# Hex_Link_Trans.net
KiCad netlist of a schematic drawn in Altium Designer
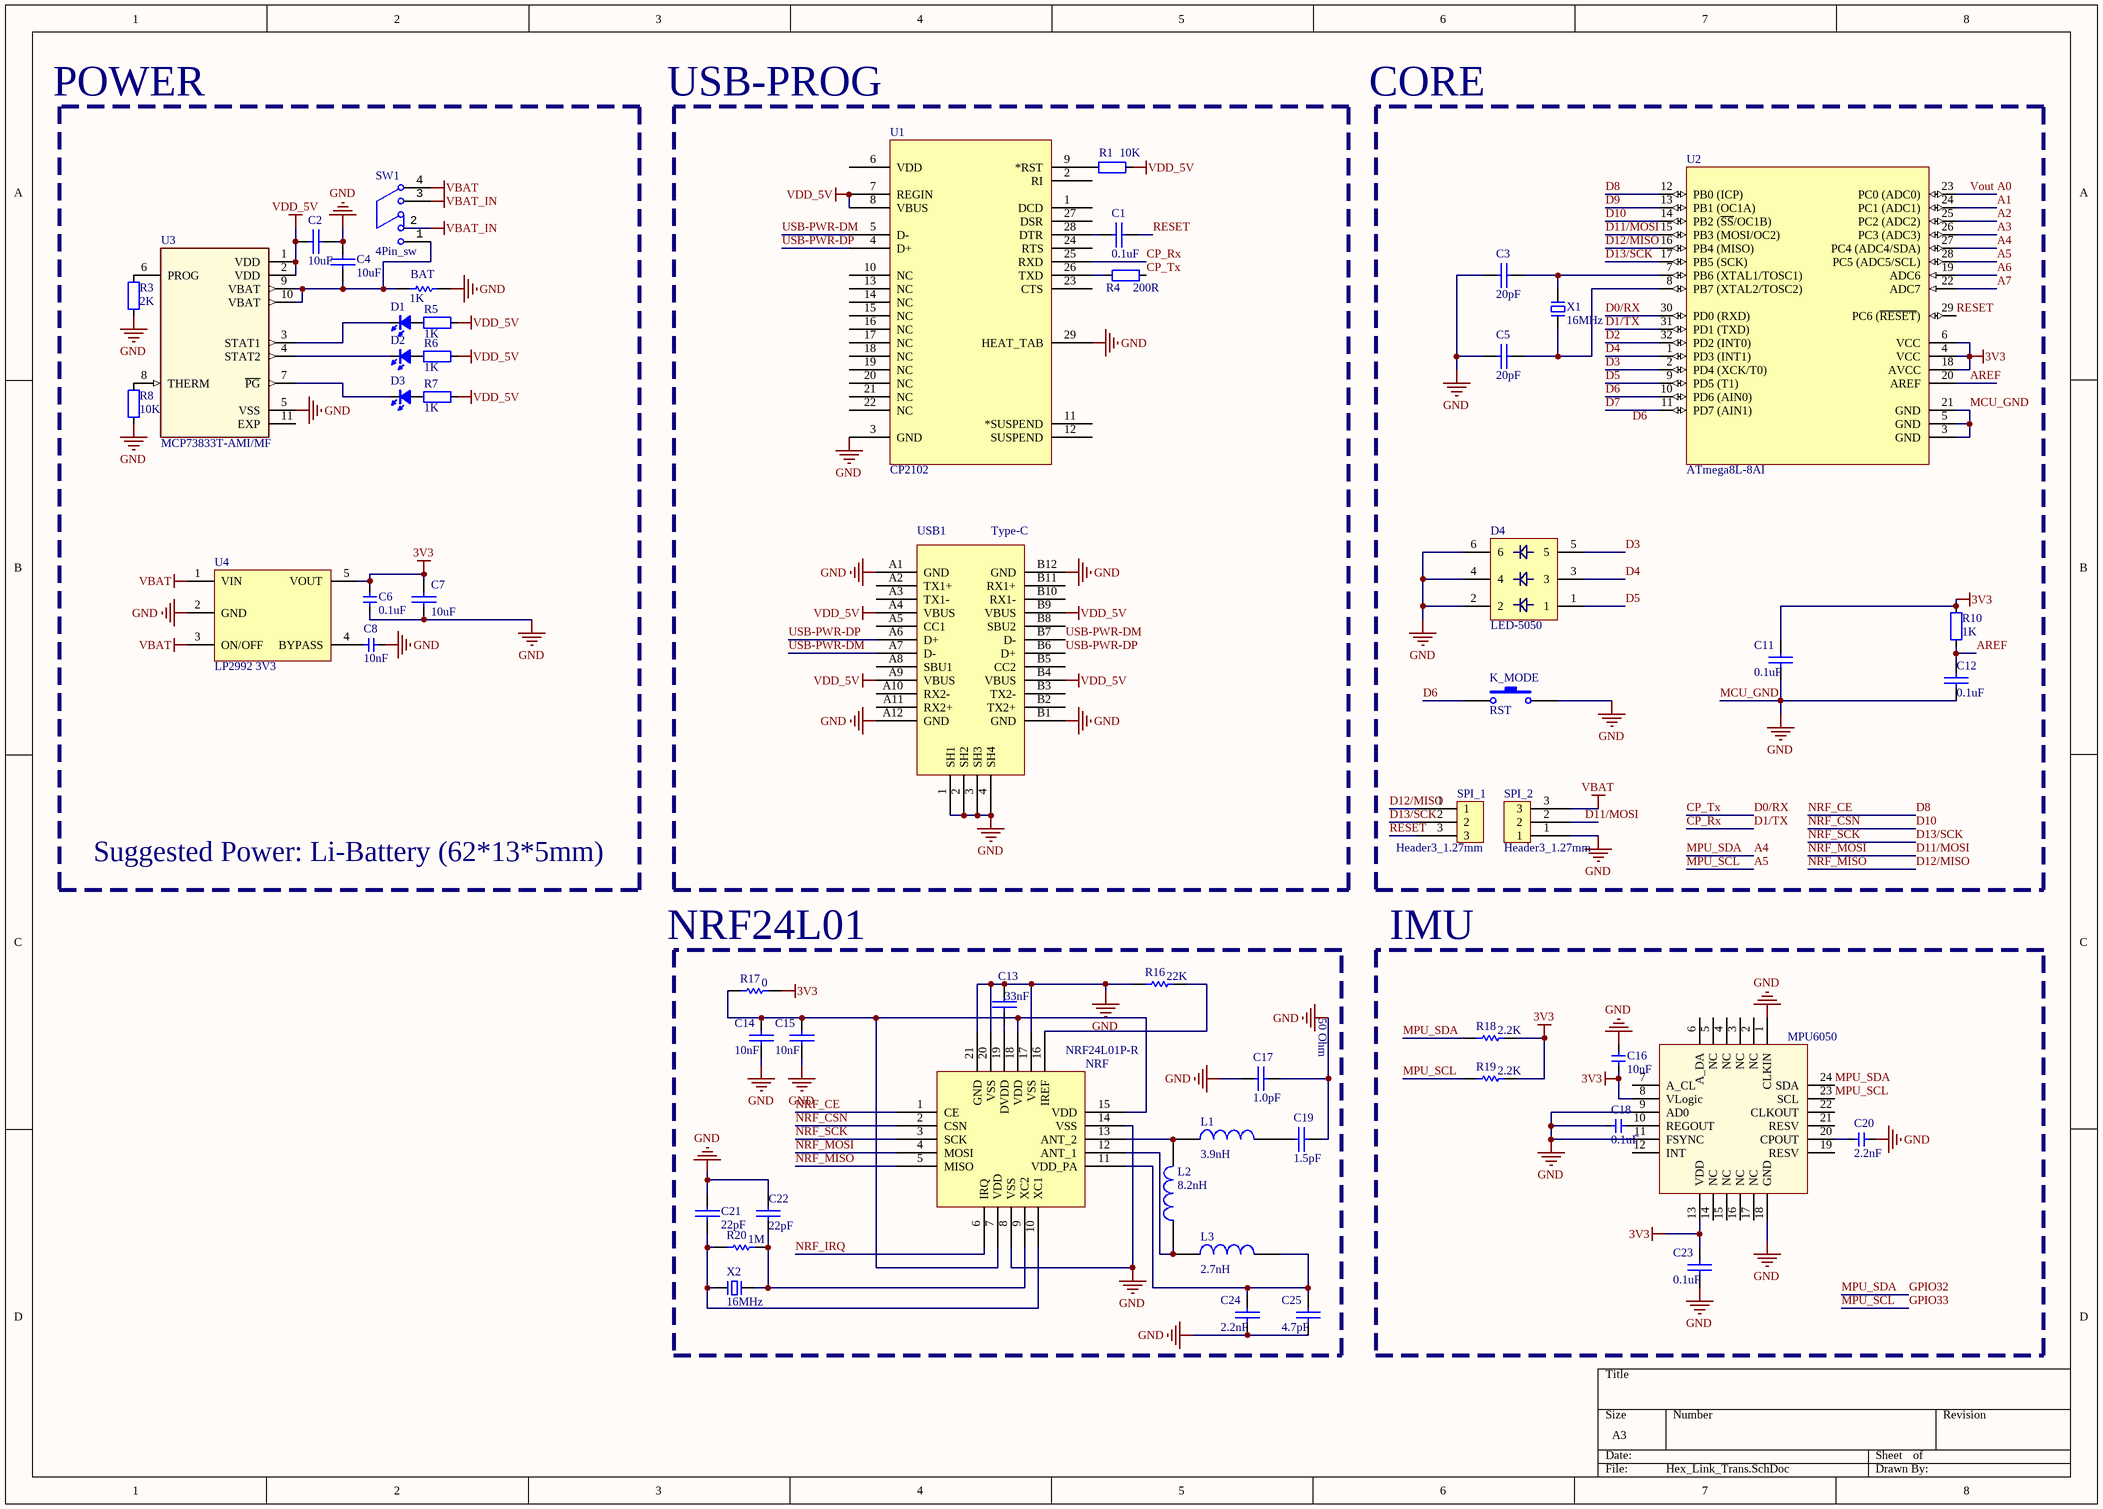
[diagram p0: Hex_Link_Trans.SchDoc]

(export (version "E")
  (design (tool "Eeschema 10.0.6"))
  (components
    (comp (ref "BAT") (value "1K") (footprint "RES_0402") (libsource (lib "电阻") (part "RES")))
    (comp (ref "C1")
      (value "0.1uF")
      (footprint "CAP_0402")
      (description "无极性电容")
      (libsource (lib "电容") (part "CAP"))
    )
    (comp (ref "C2")
      (value "10uF")
      (footprint "CAP_0402")
      (description "无极性电容")
      (libsource (lib "电容") (part "CAP"))
    )
    (comp (ref "C3")
      (value "20pF")
      (footprint "CAP_0402")
      (description "无极性电容")
      (libsource (lib "电容") (part "CAP"))
    )
    (comp (ref "C4")
      (value "10uF")
      (footprint "CAP_0402")
      (description "无极性电容")
      (libsource (lib "电容") (part "CAP"))
    )
    (comp (ref "C5")
      (value "20pF")
      (footprint "CAP_0402")
      (description "无极性电容")
      (libsource (lib "电容") (part "CAP"))
    )
    (comp (ref "C6")
      (value "0.1uF")
      (footprint "CAP_0402")
      (description "Capacitor")
      (libsource (lib "MyPcbLib") (part "电容-0402"))
    )
    (comp (ref "C7")
      (value "10uF")
      (footprint "CAP_0402")
      (description "无极性电容")
      (libsource (lib "电容") (part "CAP"))
    )
    (comp (ref "C8")
      (value "10nF")
      (footprint "CAP_0402")
      (description "Capacitor")
      (libsource (lib "MyPcbLib") (part "电容-0402"))
    )
    (comp (ref "C11")
      (value "0.1uF")
      (footprint "CAP_0402")
      (description "无极性电容")
      (libsource (lib "电容") (part "CAP"))
    )
    (comp (ref "C12")
      (value "0.1uF")
      (footprint "CAP_0402")
      (description "无极性电容")
      (libsource (lib "电容") (part "CAP"))
    )
    (comp (ref "C13")
      (value "33nF")
      (footprint "CAP_0402")
      (description "无极性电容")
      (libsource (lib "电容") (part "CAP"))
    )
    (comp (ref "C14")
      (value "10nF")
      (footprint "CAP_0402")
      (description "无极性电容")
      (libsource (lib "电容") (part "CAP"))
    )
    (comp (ref "C15")
      (value "10nF")
      (footprint "CAP_0402")
      (description "无极性电容")
      (libsource (lib "电容") (part "CAP"))
    )
    (comp (ref "C16")
      (value "10nF")
      (footprint "CAP_0402")
      (description "Capacitor")
      (libsource (lib "MyPcbLib") (part "电容-0402"))
    )
    (comp (ref "C17")
      (value "1.0pF")
      (footprint "CAP_0402")
      (description "无极性电容")
      (libsource (lib "电容") (part "CAP"))
    )
    (comp (ref "C18")
      (value "0.1uF")
      (footprint "CAP_0402")
      (description "Capacitor")
      (libsource (lib "MyPcbLib") (part "电容-0402"))
    )
    (comp (ref "C19")
      (value "1.5pF")
      (footprint "CAP_0402")
      (description "无极性电容")
      (libsource (lib "电容") (part "CAP"))
    )
    (comp (ref "C20")
      (value "2.2nF")
      (footprint "CAP_0402")
      (description "Capacitor")
      (libsource (lib "MyPcbLib") (part "电容-0402"))
    )
    (comp (ref "C21")
      (value "22pF")
      (footprint "CAP_0402")
      (description "无极性电容")
      (libsource (lib "电容") (part "CAP"))
    )
    (comp (ref "C22")
      (value "22pF")
      (footprint "CAP_0402")
      (description "无极性电容")
      (libsource (lib "电容") (part "CAP"))
    )
    (comp (ref "C23")
      (value "0.1uF")
      (footprint "CAP_0402")
      (description "无极性电容")
      (libsource (lib "电容") (part "CAP"))
    )
    (comp (ref "C24")
      (value "2.2nF")
      (footprint "CAP_0402")
      (description "无极性电容")
      (libsource (lib "电容") (part "CAP"))
    )
    (comp (ref "C25")
      (value "4.7pF")
      (footprint "CAP_0402")
      (description "无极性电容")
      (libsource (lib "电容") (part "CAP"))
    )
    (comp (ref "D1")
      (value "color?")
      (footprint "LED_0402_RED")
      (description "LED")
      (libsource (lib "KitSprout") (part "LED_0402"))
    )
    (comp (ref "D2")
      (value "color?")
      (footprint "LED_0402_RED")
      (description "LED")
      (libsource (lib "KitSprout") (part "LED_0402"))
    )
    (comp (ref "D3")
      (value "color?")
      (footprint "LED_0402_RED")
      (description "LED")
      (libsource (lib "KitSprout") (part "LED_0402"))
    )
    (comp (ref "D4") (value "LED-5050") (footprint "LED-5050W") (libsource (lib "LED") (part "LED-5050")))
    (comp (ref "K_MODE")
      (value "RST")
      (footprint "SW_PB")
      (description "Switch")
      (fields (field (name "PUBLISHER") "Altium Limited"))
      (libsource (lib "未分类IC") (part "SW-PB"))
    )
    (comp (ref "L1")
      (value "3.9nH")
      (footprint "0402L_2")
      (description "INDUCTOR")
      (libsource (lib "") (part "INDUCTOR_1"))
    )
    (comp (ref "L2")
      (value "8.2nH")
      (footprint "0402L_2")
      (description "INDUCTOR")
      (libsource (lib "电感") (part "INDUCTOR"))
    )
    (comp (ref "L3")
      (value "2.7nH")
      (footprint "0402L_2")
      (description "INDUCTOR")
      (libsource (lib "") (part "INDUCTOR_1"))
    )
    (comp (ref "NRF")
      (value "NRF24L01P-R")
      (footprint "QFN20")
      (libsource (lib "未分类IC") (part "NRF24L01P-R"))
    )
    (comp (ref "R1")
      (value "10K")
      (footprint "RES_0402")
      (description "Resistor")
      (libsource (lib "MyPcbLib") (part "电阻-0402"))
    )
    (comp (ref "R3")
      (value "2K")
      (footprint "RES_0402")
      (description "Resistor")
      (libsource (lib "") (part "电阻-0402_1"))
    )
    (comp (ref "R4")
      (value "200R")
      (footprint "RES_0402")
      (description "Resistor")
      (libsource (lib "MyPcbLib") (part "电阻-0402"))
    )
    (comp (ref "R5")
      (value "1K")
      (footprint "RES_0402")
      (description "Resistor")
      (libsource (lib "MyPcbLib") (part "电阻-0402"))
    )
    (comp (ref "R6")
      (value "1K")
      (footprint "RES_0402")
      (description "Resistor")
      (libsource (lib "MyPcbLib") (part "电阻-0402"))
    )
    (comp (ref "R7")
      (value "1K")
      (footprint "RES_0402")
      (description "Resistor")
      (libsource (lib "MyPcbLib") (part "电阻-0402"))
    )
    (comp (ref "R8")
      (value "10K")
      (footprint "RES_0402")
      (description "Resistor")
      (libsource (lib "") (part "电阻-0402_1"))
    )
    (comp (ref "R10")
      (value "1K")
      (footprint "RES_0402")
      (description "Resistor")
      (libsource (lib "") (part "电阻-0402_2"))
    )
    (comp (ref "R16") (value "22K") (footprint "RES_0402") (libsource (lib "电阻") (part "RES")))
    (comp (ref "R17") (value "0") (footprint "RES_0402") (libsource (lib "电阻") (part "RES")))
    (comp (ref "R18") (value "2.2K") (footprint "RES_0402") (libsource (lib "电阻") (part "RES")))
    (comp (ref "R19") (value "2.2K") (footprint "RES_0402") (libsource (lib "电阻") (part "RES")))
    (comp (ref "R20") (value "1M") (footprint "RES_0402") (libsource (lib "电阻") (part "RES")))
    (comp (ref "SPI_1")
      (value "Header3_1.27mm")
      (footprint "HEADER3_1.27mm")
      (libsource (lib "") (part "Header3_1.27mm_1"))
    )
    (comp (ref "SPI_2")
      (value "Header3_1.27mm")
      (footprint "HEADER3_1.27mm")
      (libsource (lib "未分类IC") (part "Header3_1.27mm"))
    )
    (comp (ref "SW1") (value "4Pin_sw") (footprint "4pin_SW") (libsource (lib "未分类IC") (part "4Pin_sw")))
    (comp (ref "U1")
      (value "CP2102")
      (footprint "QFN-28")
      (description "USB转TTL")
      (libsource (lib "mLib") (part "CP2102"))
    )
    (comp (ref "U2")
      (value "ATmega8L-8AI")
      (footprint "32A_N")
      (description "8-Bit AVR Microcontroller with 8K Bytes of In-System Programmable Flash Memory")
      (fields (field (name "PUBLISHER") "Altium Limited"))
      (libsource (lib "Atmel Microcontroller 8-Bit AVR") (part "ATmega8L-8AI"))
    )
    (comp (ref "U3")
      (value "MCP73833T-AMI/MF")
      (footprint "QFN_10_L")
      (description "Linear Charge Management Controller Li-Ion/Li-Pol 1mA 4.2V/4.35V/4.4V/4.5V 10-Pin DFN EP T/R")
      (fields (field (name "MF") "Microchip"))
      (libsource (lib "mLib") (part "MCP73833T"))
    )
    (comp (ref "U4")
      (value "LP2992 3V3")
      (footprint "SOT23-5")
      (description "LDO")
      (libsource (lib "MyPcbLib") (part "LP2992"))
    )
    (comp (ref "U5")
      (value "MPU6050")
      (footprint "QFN-24")
      (description "六轴传感器")
      (libsource (lib "mLib") (part "MPU6050"))
    )
    (comp (ref "USB1")
      (value "Type-C")
      (footprint "Type-C-TOP")
      (libsource (lib "MyPcbLib") (part "USB-Type-C-TOP"))
    )
    (comp (ref "X1")
      (value "16MHz")
      (footprint "OSC 5032-2P")
      (description "2脚无源脚晶振")
      (libsource (lib "晶振") (part "XTAL-2P"))
    )
    (comp (ref "X2")
      (value "16MHz")
      (footprint "OSC 5032-2P")
      (description "2脚无源脚晶振")
      (libsource (lib "晶振") (part "XTAL-2P"))
    )
  )
  (nets
    (net (code "1") (name "/A0") (class "Default")
      (node (ref "U2") (pin "23") (pinfunction "PC0_(ADC0)_23") (pintype "bidirectional"))
    )
    (net (code "2") (name "/A1") (class "Default")
      (node (ref "U2") (pin "24") (pinfunction "PC1_(ADC1)_24") (pintype "bidirectional"))
    )
    (net (code "3") (name "/A2") (class "Default")
      (node (ref "U2") (pin "25") (pinfunction "PC2_(ADC2)_25") (pintype "bidirectional"))
    )
    (net (code "4") (name "/A3") (class "Default")
      (node (ref "U2") (pin "26") (pinfunction "PC3_(ADC3)_26") (pintype "bidirectional"))
    )
    (net (code "5") (name "/A4") (class "Default")
      (node (ref "R18") (pin "1") (pinfunction "1_1") (pintype "passive"))
      (node (ref "U2") (pin "27") (pinfunction "PC4_(ADC4/SDA)_27") (pintype "bidirectional"))
      (node (ref "U5") (pin "24") (pinfunction "SDA_24") (pintype "passive"))
    )
    (net (code "6") (name "/A5") (class "Default")
      (node (ref "R19") (pin "1") (pinfunction "1_1") (pintype "passive"))
      (node (ref "U2") (pin "28") (pinfunction "PC5_(ADC5/SCL)_28") (pintype "bidirectional"))
      (node (ref "U5") (pin "23") (pinfunction "SCL_23") (pintype "passive"))
    )
    (net (code "7") (name "/A6") (class "Default")
      (node (ref "U2") (pin "19") (pinfunction "ADC6_19") (pintype "input"))
    )
    (net (code "8") (name "/A7") (class "Default")
      (node (ref "U2") (pin "22") (pinfunction "ADC7_22") (pintype "input"))
    )
    (net (code "9") (name "/AREF") (class "Default")
      (node (ref "C12") (pin "1") (pinfunction "1_1") (pintype "passive"))
      (node (ref "R10") (pin "2") (pinfunction "2_2") (pintype "passive"))
      (node (ref "U2") (pin "20") (pinfunction "AREF_20") (pintype "passive"))
    )
    (net (code "10") (name "/CP_Rx") (class "Default")
      (node (ref "U1") (pin "25") (pinfunction "RXD_25") (pintype "passive"))
      (node (ref "U2") (pin "31") (pinfunction "PD1_(TXD)_31") (pintype "bidirectional"))
    )
    (net (code "11") (name "/CP_Tx") (class "Default")
      (node (ref "R4") (pin "1") (pinfunction "1_1") (pintype "passive"))
      (node (ref "U2") (pin "30") (pinfunction "PD0_(RXD)_30") (pintype "bidirectional"))
    )
    (net (code "12") (name "/D2") (class "Default")
      (node (ref "U2") (pin "32") (pinfunction "PD2_(INT0)_32") (pintype "bidirectional"))
    )
    (net (code "13") (name "/D3") (class "Default")
      (node (ref "D4") (pin "5") (pinfunction "5_5") (pintype "passive"))
      (node (ref "U2") (pin "2") (pinfunction "PD4_(XCK/T0)_2") (pintype "bidirectional"))
    )
    (net (code "14") (name "/D4") (class "Default")
      (node (ref "D4") (pin "3") (pinfunction "3_3") (pintype "passive"))
      (node (ref "U2") (pin "1") (pinfunction "PD3_(INT1)_1") (pintype "bidirectional"))
    )
    (net (code "15") (name "/D5") (class "Default")
      (node (ref "D4") (pin "1") (pinfunction "1_1") (pintype "passive"))
      (node (ref "U2") (pin "9") (pinfunction "PD5_(T1)_9") (pintype "bidirectional"))
    )
    (net (code "16") (name "/D6") (class "Default")
      (node (ref "K_MODE") (pin "1") (pinfunction "1_1") (pintype "passive"))
      (node (ref "U2") (pin "10") (pinfunction "PD6_(AIN0)_10") (pintype "bidirectional"))
    )
    (net (code "17") (name "/D7") (class "Default")
      (node (ref "U2") (pin "11") (pinfunction "PD7_(AIN1)_11") (pintype "bidirectional"))
    )
    (net (code "18") (name "/D8") (class "Default")
      (node (ref "NRF") (pin "1") (pinfunction "CE_1") (pintype "passive"))
      (node (ref "U2") (pin "12") (pinfunction "PB0_(ICP)_12") (pintype "bidirectional"))
    )
    (net (code "19") (name "/D9") (class "Default")
      (node (ref "U2") (pin "13") (pinfunction "PB1_(OC1A)_13") (pintype "bidirectional"))
    )
    (net (code "20") (name "/D10") (class "Default")
      (node (ref "NRF") (pin "2") (pinfunction "CSN_2") (pintype "passive"))
      (node (ref "U2") (pin "14") (pinfunction "PB2_(~{SS}/OC1B)_14") (pintype "bidirectional"))
    )
    (net (code "21") (name "/D11{slash}MOSI") (class "Default")
      (node (ref "NRF") (pin "4") (pinfunction "MOSI_4") (pintype "passive"))
      (node (ref "SPI_2") (pin "2") (pinfunction "2_2") (pintype "passive"))
      (node (ref "U2") (pin "15") (pinfunction "PB3_(MOSI/OC2)_15") (pintype "bidirectional"))
    )
    (net (code "22") (name "/D12{slash}MISO") (class "Default")
      (node (ref "NRF") (pin "5") (pinfunction "MISO_5") (pintype "passive"))
      (node (ref "SPI_1") (pin "1") (pinfunction "1_1") (pintype "passive"))
      (node (ref "U2") (pin "16") (pinfunction "PB4_(MISO)_16") (pintype "bidirectional"))
    )
    (net (code "23") (name "/D13{slash}SCK") (class "Default")
      (node (ref "NRF") (pin "3") (pinfunction "SCK_3") (pintype "passive"))
      (node (ref "SPI_1") (pin "2") (pinfunction "2_2") (pintype "passive"))
      (node (ref "U2") (pin "17") (pinfunction "PB5_(SCK)_17") (pintype "bidirectional"))
    )
    (net (code "24") (name "/NRF_IRQ") (class "Default")
      (node (ref "NRF") (pin "6") (pinfunction "IRQ_6") (pintype "passive"))
    )
    (net (code "25") (name "/RESET") (class "Default")
      (node (ref "C1") (pin "1") (pinfunction "1_1") (pintype "passive"))
      (node (ref "SPI_1") (pin "3") (pinfunction "3_3") (pintype "passive"))
      (node (ref "U2") (pin "29") (pinfunction "PC6_(~{RESET})_29") (pintype "bidirectional"))
    )
    (net (code "26") (name "/USB-PWR-DM") (class "Default")
      (node (ref "U1") (pin "5") (pinfunction "D-_5") (pintype "passive"))
      (node (ref "USB1") (pin "A7") (pinfunction "D-_A7") (pintype "passive"))
      (node (ref "USB1") (pin "B7") (pinfunction "D-_B7") (pintype "passive"))
    )
    (net (code "27") (name "/USB-PWR-DP") (class "Default")
      (node (ref "U1") (pin "4") (pinfunction "D+_4") (pintype "passive"))
      (node (ref "USB1") (pin "A6") (pinfunction "D+_A6") (pintype "passive"))
      (node (ref "USB1") (pin "B6") (pinfunction "D+_B6") (pintype "passive"))
    )
    (net (code "28") (name "3V3") (class "Default")
      (node (ref "C11") (pin "1") (pinfunction "1_1") (pintype "passive"))
      (node (ref "C16") (pin "1") (pinfunction "1_1") (pintype "passive"))
      (node (ref "C23") (pin "1") (pinfunction "1_1") (pintype "passive"))
      (node (ref "C6") (pin "1") (pinfunction "1_1") (pintype "passive"))
      (node (ref "C7") (pin "1") (pinfunction "1_1") (pintype "passive"))
      (node (ref "R10") (pin "1") (pinfunction "1_1") (pintype "passive"))
      (node (ref "R17") (pin "2") (pinfunction "2_2") (pintype "passive"))
      (node (ref "R18") (pin "2") (pinfunction "2_2") (pintype "passive"))
      (node (ref "R19") (pin "2") (pinfunction "2_2") (pintype "passive"))
      (node (ref "U2") (pin "18") (pinfunction "AVCC_18") (pintype "power_in"))
      (node (ref "U2") (pin "4") (pinfunction "VCC_4") (pintype "power_in"))
      (node (ref "U2") (pin "6") (pinfunction "VCC_6") (pintype "power_in"))
      (node (ref "U4") (pin "5") (pinfunction "VOUT_5") (pintype "passive"))
      (node (ref "U5") (pin "13") (pinfunction "VDD_13") (pintype "passive"))
      (node (ref "U5") (pin "8") (pinfunction "VLogic_8") (pintype "passive"))
    )
    (net (code "29") (name "GND") (class "Default")
      (node (ref "BAT") (pin "2") (pinfunction "2_2") (pintype "passive"))
      (node (ref "C11") (pin "2") (pinfunction "2_2") (pintype "passive"))
      (node (ref "C12") (pin "2") (pinfunction "2_2") (pintype "passive"))
      (node (ref "C13") (pin "1") (pinfunction "1_1") (pintype "passive"))
      (node (ref "C14") (pin "2") (pinfunction "2_2") (pintype "passive"))
      (node (ref "C15") (pin "2") (pinfunction "2_2") (pintype "passive"))
      (node (ref "C16") (pin "2") (pinfunction "2_2") (pintype "passive"))
      (node (ref "C17") (pin "1") (pinfunction "1_1") (pintype "passive"))
      (node (ref "C17") (pin "2") (pinfunction "2_2") (pintype "passive"))
      (node (ref "C18") (pin "2") (pinfunction "2_2") (pintype "passive"))
      (node (ref "C19") (pin "2") (pinfunction "2_2") (pintype "passive"))
      (node (ref "C2") (pin "2") (pinfunction "2_2") (pintype "passive"))
      (node (ref "C20") (pin "1") (pinfunction "1_1") (pintype "passive"))
      (node (ref "C21") (pin "2") (pinfunction "2_2") (pintype "passive"))
      (node (ref "C22") (pin "1") (pinfunction "1_1") (pintype "passive"))
      (node (ref "C23") (pin "2") (pinfunction "2_2") (pintype "passive"))
      (node (ref "C24") (pin "2") (pinfunction "2_2") (pintype "passive"))
      (node (ref "C25") (pin "2") (pinfunction "2_2") (pintype "passive"))
      (node (ref "C3") (pin "2") (pinfunction "2_2") (pintype "passive"))
      (node (ref "C4") (pin "1") (pinfunction "1_1") (pintype "passive"))
      (node (ref "C5") (pin "2") (pinfunction "2_2") (pintype "passive"))
      (node (ref "C6") (pin "2") (pinfunction "2_2") (pintype "passive"))
      (node (ref "C7") (pin "2") (pinfunction "2_2") (pintype "passive"))
      (node (ref "C8") (pin "1") (pinfunction "1_1") (pintype "passive"))
      (node (ref "D4") (pin "2") (pinfunction "2_2") (pintype "passive"))
      (node (ref "D4") (pin "4") (pinfunction "4_4") (pintype "passive"))
      (node (ref "D4") (pin "6") (pinfunction "6_6") (pintype "passive"))
      (node (ref "K_MODE") (pin "2") (pinfunction "2_2") (pintype "passive"))
      (node (ref "NRF") (pin "14") (pinfunction "VSS_14") (pintype "passive"))
      (node (ref "NRF") (pin "17") (pinfunction "VSS_17") (pintype "passive"))
      (node (ref "NRF") (pin "20") (pinfunction "VSS_20") (pintype "passive"))
      (node (ref "NRF") (pin "21") (pinfunction "GND_21") (pintype "passive"))
      (node (ref "NRF") (pin "8") (pinfunction "VSS_8") (pintype "passive"))
      (node (ref "R16") (pin "1") (pinfunction "1_1") (pintype "passive"))
      (node (ref "R3") (pin "1") (pinfunction "1_1") (pintype "passive"))
      (node (ref "R8") (pin "1") (pinfunction "1_1") (pintype "passive"))
      (node (ref "SPI_2") (pin "1") (pinfunction "1_1") (pintype "passive"))
      (node (ref "U1") (pin "29") (pinfunction "HEAT_TAB_29") (pintype "passive"))
      (node (ref "U1") (pin "3") (pinfunction "GND_3") (pintype "passive"))
      (node (ref "U2") (pin "21") (pinfunction "GND_21") (pintype "power_in"))
      (node (ref "U2") (pin "3") (pinfunction "GND_3") (pintype "power_in"))
      (node (ref "U2") (pin "5") (pinfunction "GND_5") (pintype "power_in"))
      (node (ref "U3") (pin "5") (pinfunction "VSS_5") (pintype "power_in"))
      (node (ref "U4") (pin "2") (pinfunction "GND_2") (pintype "passive"))
      (node (ref "U5") (pin "1") (pinfunction "CLKIN_1") (pintype "passive"))
      (node (ref "U5") (pin "11") (pinfunction "FSYNC_11") (pintype "passive"))
      (node (ref "U5") (pin "18") (pinfunction "GND_18") (pintype "passive"))
      (node (ref "U5") (pin "9") (pinfunction "AD0_9") (pintype "passive"))
      (node (ref "USB1") (pin "1") (pinfunction "SH1_1") (pintype "passive"))
      (node (ref "USB1") (pin "2") (pinfunction "SH2_2") (pintype "passive"))
      (node (ref "USB1") (pin "3") (pinfunction "SH3_3") (pintype "passive"))
      (node (ref "USB1") (pin "4") (pinfunction "SH4_4") (pintype "passive"))
      (node (ref "USB1") (pin "A1") (pinfunction "GND_A1") (pintype "passive"))
      (node (ref "USB1") (pin "A12") (pinfunction "GND_A12") (pintype "passive"))
      (node (ref "USB1") (pin "B1") (pinfunction "GND_B1") (pintype "passive"))
      (node (ref "USB1") (pin "B12") (pinfunction "GND_B12") (pintype "passive"))
    )
    (net (code "30") (name "Net-(BAT-Pad1)") (class "Default")
      (node (ref "BAT") (pin "1") (pinfunction "1_1") (pintype "passive"))
      (node (ref "C4") (pin "2") (pinfunction "2_2") (pintype "passive"))
      (node (ref "SW1") (pin "1") (pinfunction "1_1") (pintype "passive"))
      (node (ref "U3") (pin "10") (pinfunction "VBAT_10") (pintype "output"))
      (node (ref "U3") (pin "9") (pinfunction "VBAT_9") (pintype "output"))
    )
    (net (code "31") (name "Net-(C14-Pad1)") (class "Default")
      (node (ref "C14") (pin "1") (pinfunction "1_1") (pintype "passive"))
      (node (ref "C15") (pin "1") (pinfunction "1_1") (pintype "passive"))
      (node (ref "NRF") (pin "15") (pinfunction "VDD_15") (pintype "passive"))
      (node (ref "NRF") (pin "18") (pinfunction "VDD_18") (pintype "passive"))
      (node (ref "NRF") (pin "7") (pinfunction "VDD_7") (pintype "passive"))
      (node (ref "R17") (pin "1") (pinfunction "1_1") (pintype "passive"))
    )
    (net (code "32") (name "Net-(C19-Pad1)") (class "Default")
      (node (ref "C19") (pin "1") (pinfunction "1_1") (pintype "passive"))
      (node (ref "L1") (pin "2") (pinfunction "2_2") (pintype "passive"))
    )
    (net (code "33") (name "Net-(D1-A)") (class "Default")
      (node (ref "D1") (pin "1") (pinfunction "A_1") (pintype "passive"))
      (node (ref "R5") (pin "2") (pinfunction "2_2") (pintype "passive"))
    )
    (net (code "34") (name "Net-(D1-K)") (class "Default")
      (node (ref "D1") (pin "2") (pinfunction "K_2") (pintype "passive"))
      (node (ref "U3") (pin "3") (pinfunction "STAT1_3") (pintype "output"))
    )
    (net (code "35") (name "Net-(D2-A)") (class "Default")
      (node (ref "D2") (pin "1") (pinfunction "A_1") (pintype "passive"))
      (node (ref "R6") (pin "2") (pinfunction "2_2") (pintype "passive"))
    )
    (net (code "36") (name "Net-(D2-K)") (class "Default")
      (node (ref "D2") (pin "2") (pinfunction "K_2") (pintype "passive"))
      (node (ref "U3") (pin "4") (pinfunction "STAT2_4") (pintype "output"))
    )
    (net (code "37") (name "Net-(D3-A)") (class "Default")
      (node (ref "D3") (pin "1") (pinfunction "A_1") (pintype "passive"))
      (node (ref "R7") (pin "2") (pinfunction "2_2") (pintype "passive"))
    )
    (net (code "38") (name "Net-(D3-K)") (class "Default")
      (node (ref "D3") (pin "2") (pinfunction "K_2") (pintype "passive"))
      (node (ref "U3") (pin "7") (pinfunction "~{PG}_7") (pintype "output"))
    )
    (net (code "39") (name "Net-(NRF-ANT_1)") (class "Default")
      (node (ref "L2") (pin "1") (pinfunction "1_1") (pintype "passive"))
      (node (ref "L3") (pin "1") (pinfunction "1_1") (pintype "passive"))
      (node (ref "NRF") (pin "12") (pinfunction "ANT_1_12") (pintype "passive"))
    )
    (net (code "40") (name "Net-(NRF-ANT_2)") (class "Default")
      (node (ref "L1") (pin "1") (pinfunction "1_1") (pintype "passive"))
      (node (ref "L2") (pin "2") (pinfunction "2_2") (pintype "passive"))
      (node (ref "NRF") (pin "13") (pinfunction "ANT_2_13") (pintype "passive"))
    )
    (net (code "41") (name "Net-(NRF-DVDD)") (class "Default")
      (node (ref "C13") (pin "2") (pinfunction "2_2") (pintype "passive"))
      (node (ref "NRF") (pin "19") (pinfunction "DVDD_19") (pintype "passive"))
    )
    (net (code "42") (name "Net-(NRF-IREF)") (class "Default")
      (node (ref "NRF") (pin "16") (pinfunction "IREF_16") (pintype "passive"))
      (node (ref "R16") (pin "2") (pinfunction "2_2") (pintype "passive"))
    )
    (net (code "43") (name "Net-(NRF-VDD_PA)") (class "Default")
      (node (ref "C24") (pin "1") (pinfunction "1_1") (pintype "passive"))
      (node (ref "C25") (pin "1") (pinfunction "1_1") (pintype "passive"))
      (node (ref "L3") (pin "2") (pinfunction "2_2") (pintype "passive"))
      (node (ref "NRF") (pin "11") (pinfunction "VDD_PA_11") (pintype "passive"))
    )
    (net (code "44") (name "Net-(NRF-XC1)") (class "Default")
      (node (ref "C21") (pin "1") (pinfunction "1_1") (pintype "passive"))
      (node (ref "NRF") (pin "10") (pinfunction "XC1_10") (pintype "passive"))
      (node (ref "R20") (pin "1") (pinfunction "1_1") (pintype "passive"))
      (node (ref "X2") (pin "1") (pinfunction "1_1") (pintype "passive"))
    )
    (net (code "45") (name "Net-(NRF-XC2)") (class "Default")
      (node (ref "C22") (pin "2") (pinfunction "2_2") (pintype "passive"))
      (node (ref "NRF") (pin "9") (pinfunction "XC2_9") (pintype "passive"))
      (node (ref "R20") (pin "2") (pinfunction "2_2") (pintype "passive"))
      (node (ref "X2") (pin "2") (pinfunction "2_2") (pintype "passive"))
    )
    (net (code "46") (name "Net-(U1-*RST)") (class "Default")
      (node (ref "R1") (pin "2") (pinfunction "2_2") (pintype "passive"))
      (node (ref "U1") (pin "9") (pinfunction "*RST_9") (pintype "passive"))
    )
    (net (code "47") (name "Net-(U1-DTR)") (class "Default")
      (node (ref "C1") (pin "2") (pinfunction "2_2") (pintype "passive"))
      (node (ref "U1") (pin "28") (pinfunction "DTR_28") (pintype "passive"))
    )
    (net (code "48") (name "Net-(U1-TXD)") (class "Default")
      (node (ref "R4") (pin "2") (pinfunction "2_2") (pintype "passive"))
      (node (ref "U1") (pin "26") (pinfunction "TXD_26") (pintype "passive"))
    )
    (net (code "49") (name "Net-(U2-PB6_(XTAL1{slash}TOSC1))") (class "Default")
      (node (ref "C3") (pin "1") (pinfunction "1_1") (pintype "passive"))
      (node (ref "U2") (pin "7") (pinfunction "PB6_(XTAL1/TOSC1)_7") (pintype "bidirectional"))
      (node (ref "X1") (pin "2") (pinfunction "2_2") (pintype "passive"))
    )
    (net (code "50") (name "Net-(U2-PB7_(XTAL2{slash}TOSC2))") (class "Default")
      (node (ref "C5") (pin "1") (pinfunction "1_1") (pintype "passive"))
      (node (ref "U2") (pin "8") (pinfunction "PB7_(XTAL2/TOSC2)_8") (pintype "bidirectional"))
      (node (ref "X1") (pin "1") (pinfunction "1_1") (pintype "passive"))
    )
    (net (code "51") (name "Net-(U3-PROG)") (class "Default")
      (node (ref "R3") (pin "2") (pinfunction "2_2") (pintype "passive"))
      (node (ref "U3") (pin "6") (pinfunction "PROG_6") (pintype "passive"))
    )
    (net (code "52") (name "Net-(U3-THERM)") (class "Default")
      (node (ref "R8") (pin "2") (pinfunction "2_2") (pintype "passive"))
      (node (ref "U3") (pin "8") (pinfunction "THERM_8") (pintype "input"))
    )
    (net (code "53") (name "Net-(U4-BYPASS)") (class "Default")
      (node (ref "C8") (pin "2") (pinfunction "2_2") (pintype "passive"))
      (node (ref "U4") (pin "4") (pinfunction "BYPASS_4") (pintype "passive"))
    )
    (net (code "54") (name "Net-(U5-CPOUT)") (class "Default")
      (node (ref "C20") (pin "2") (pinfunction "2_2") (pintype "passive"))
      (node (ref "U5") (pin "20") (pinfunction "CPOUT_20") (pintype "passive"))
    )
    (net (code "55") (name "Net-(U5-REGOUT)") (class "Default")
      (node (ref "C18") (pin "1") (pinfunction "1_1") (pintype "passive"))
      (node (ref "U5") (pin "10") (pinfunction "REGOUT_10") (pintype "passive"))
    )
    (net (code "56") (name "VBAT") (class "Default")
      (node (ref "SPI_2") (pin "3") (pinfunction "3_3") (pintype "passive"))
      (node (ref "SW1") (pin "4") (pinfunction "4_4") (pintype "passive"))
      (node (ref "U4") (pin "1") (pinfunction "VIN_1") (pintype "passive"))
      (node (ref "U4") (pin "3") (pinfunction "ON/OFF_3") (pintype "passive"))
    )
    (net (code "57") (name "VBAT_IN") (class "Default")
      (node (ref "SW1") (pin "2") (pinfunction "2_2") (pintype "passive"))
      (node (ref "SW1") (pin "3") (pinfunction "3_3") (pintype "passive"))
    )
    (net (code "58") (name "VDD_5V") (class "Default")
      (node (ref "C2") (pin "1") (pinfunction "1_1") (pintype "passive"))
      (node (ref "R1") (pin "1") (pinfunction "1_1") (pintype "passive"))
      (node (ref "R5") (pin "1") (pinfunction "1_1") (pintype "passive"))
      (node (ref "R6") (pin "1") (pinfunction "1_1") (pintype "passive"))
      (node (ref "R7") (pin "1") (pinfunction "1_1") (pintype "passive"))
      (node (ref "U1") (pin "7") (pinfunction "REGIN_7") (pintype "passive"))
      (node (ref "U1") (pin "8") (pinfunction "VBUS_8") (pintype "passive"))
      (node (ref "U3") (pin "1") (pinfunction "VDD_1") (pintype "power_in"))
      (node (ref "U3") (pin "2") (pinfunction "VDD_2") (pintype "power_in"))
      (node (ref "USB1") (pin "A4") (pinfunction "VBUS_A4") (pintype "passive"))
      (node (ref "USB1") (pin "A9") (pinfunction "VBUS_A9") (pintype "passive"))
      (node (ref "USB1") (pin "B4") (pinfunction "VBUS_B4") (pintype "passive"))
      (node (ref "USB1") (pin "B9") (pinfunction "VBUS_B9") (pintype "passive"))
    )
    (net (code "59") (name "unconnected-(U1-*SUSPEND-Pad11)") (class "Default")
      (node (ref "U1") (pin "11") (pinfunction "*SUSPEND_11") (pintype "passive"))
    )
    (net (code "60") (name "unconnected-(U1-CTS-Pad23)") (class "Default")
      (node (ref "U1") (pin "23") (pinfunction "CTS_23") (pintype "passive"))
    )
    (net (code "61") (name "unconnected-(U1-DCD-Pad1)") (class "Default")
      (node (ref "U1") (pin "1") (pinfunction "DCD_1") (pintype "passive"))
    )
    (net (code "62") (name "unconnected-(U1-DSR-Pad27)") (class "Default")
      (node (ref "U1") (pin "27") (pinfunction "DSR_27") (pintype "passive"))
    )
    (net (code "63") (name "unconnected-(U1-NC-Pad10)") (class "Default")
      (node (ref "U1") (pin "10") (pinfunction "NC_10") (pintype "passive"))
    )
    (net (code "64") (name "unconnected-(U1-NC-Pad13)") (class "Default")
      (node (ref "U1") (pin "13") (pinfunction "NC_13") (pintype "passive"))
    )
    (net (code "65") (name "unconnected-(U1-NC-Pad14)") (class "Default")
      (node (ref "U1") (pin "14") (pinfunction "NC_14") (pintype "passive"))
    )
    (net (code "66") (name "unconnected-(U1-NC-Pad15)") (class "Default")
      (node (ref "U1") (pin "15") (pinfunction "NC_15") (pintype "passive"))
    )
    (net (code "67") (name "unconnected-(U1-NC-Pad16)") (class "Default")
      (node (ref "U1") (pin "16") (pinfunction "NC_16") (pintype "passive"))
    )
    (net (code "68") (name "unconnected-(U1-NC-Pad17)") (class "Default")
      (node (ref "U1") (pin "17") (pinfunction "NC_17") (pintype "passive"))
    )
    (net (code "69") (name "unconnected-(U1-NC-Pad18)") (class "Default")
      (node (ref "U1") (pin "18") (pinfunction "NC_18") (pintype "passive"))
    )
    (net (code "70") (name "unconnected-(U1-NC-Pad19)") (class "Default")
      (node (ref "U1") (pin "19") (pinfunction "NC_19") (pintype "passive"))
    )
    (net (code "71") (name "unconnected-(U1-NC-Pad20)") (class "Default")
      (node (ref "U1") (pin "20") (pinfunction "NC_20") (pintype "passive"))
    )
    (net (code "72") (name "unconnected-(U1-NC-Pad21)") (class "Default")
      (node (ref "U1") (pin "21") (pinfunction "NC_21") (pintype "passive"))
    )
    (net (code "73") (name "unconnected-(U1-NC-Pad22)") (class "Default")
      (node (ref "U1") (pin "22") (pinfunction "NC_22") (pintype "passive"))
    )
    (net (code "74") (name "unconnected-(U1-RI-Pad2)") (class "Default")
      (node (ref "U1") (pin "2") (pinfunction "RI_2") (pintype "passive"))
    )
    (net (code "75") (name "unconnected-(U1-RTS-Pad24)") (class "Default")
      (node (ref "U1") (pin "24") (pinfunction "RTS_24") (pintype "passive"))
    )
    (net (code "76") (name "unconnected-(U1-SUSPEND-Pad12)") (class "Default")
      (node (ref "U1") (pin "12") (pinfunction "SUSPEND_12") (pintype "passive"))
    )
    (net (code "77") (name "unconnected-(U1-VDD-Pad6)") (class "Default")
      (node (ref "U1") (pin "6") (pinfunction "VDD_6") (pintype "passive"))
    )
    (net (code "78") (name "unconnected-(U3-EXP-Pad11)") (class "Default")
      (node (ref "U3") (pin "11") (pinfunction "EXP_11") (pintype "passive"))
    )
    (net (code "79") (name "unconnected-(U5-A_CL-Pad7)") (class "Default")
      (node (ref "U5") (pin "7") (pinfunction "A_CL_7") (pintype "passive"))
    )
    (net (code "80") (name "unconnected-(U5-A_DA-Pad6)") (class "Default")
      (node (ref "U5") (pin "6") (pinfunction "A_DA_6") (pintype "passive"))
    )
    (net (code "81") (name "unconnected-(U5-CLKOUT-Pad22)") (class "Default")
      (node (ref "U5") (pin "22") (pinfunction "CLKOUT_22") (pintype "passive"))
    )
    (net (code "82") (name "unconnected-(U5-INT-Pad12)") (class "Default")
      (node (ref "U5") (pin "12") (pinfunction "INT_12") (pintype "passive"))
    )
    (net (code "83") (name "unconnected-(U5-NC-Pad2)") (class "Default")
      (node (ref "U5") (pin "2") (pinfunction "NC_2") (pintype "passive"))
    )
    (net (code "84") (name "unconnected-(U5-NC-Pad3)") (class "Default")
      (node (ref "U5") (pin "3") (pinfunction "NC_3") (pintype "passive"))
    )
    (net (code "85") (name "unconnected-(U5-NC-Pad4)") (class "Default")
      (node (ref "U5") (pin "4") (pinfunction "NC_4") (pintype "passive"))
    )
    (net (code "86") (name "unconnected-(U5-NC-Pad5)") (class "Default")
      (node (ref "U5") (pin "5") (pinfunction "NC_5") (pintype "passive"))
    )
    (net (code "87") (name "unconnected-(U5-NC-Pad14)") (class "Default")
      (node (ref "U5") (pin "14") (pinfunction "NC_14") (pintype "passive"))
    )
    (net (code "88") (name "unconnected-(U5-NC-Pad15)") (class "Default")
      (node (ref "U5") (pin "15") (pinfunction "NC_15") (pintype "passive"))
    )
    (net (code "89") (name "unconnected-(U5-NC-Pad16)") (class "Default")
      (node (ref "U5") (pin "16") (pinfunction "NC_16") (pintype "passive"))
    )
    (net (code "90") (name "unconnected-(U5-NC-Pad17)") (class "Default")
      (node (ref "U5") (pin "17") (pinfunction "NC_17") (pintype "passive"))
    )
    (net (code "91") (name "unconnected-(U5-RESV-Pad19)") (class "Default")
      (node (ref "U5") (pin "19") (pinfunction "RESV_19") (pintype "passive"))
    )
    (net (code "92") (name "unconnected-(U5-RESV-Pad21)") (class "Default")
      (node (ref "U5") (pin "21") (pinfunction "RESV_21") (pintype "passive"))
    )
    (net (code "93") (name "unconnected-(USB1-CC1-PadA5)") (class "Default")
      (node (ref "USB1") (pin "A5") (pinfunction "CC1_A5") (pintype "passive"))
    )
    (net (code "94") (name "unconnected-(USB1-CC2-PadB5)") (class "Default")
      (node (ref "USB1") (pin "B5") (pinfunction "CC2_B5") (pintype "passive"))
    )
    (net (code "95") (name "unconnected-(USB1-RX1+-PadB11)") (class "Default")
      (node (ref "USB1") (pin "B11") (pinfunction "RX1+_B11") (pintype "passive"))
    )
    (net (code "96") (name "unconnected-(USB1-RX1--PadB10)") (class "Default")
      (node (ref "USB1") (pin "B10") (pinfunction "RX1-_B10") (pintype "passive"))
    )
    (net (code "97") (name "unconnected-(USB1-RX2+-PadA11)") (class "Default")
      (node (ref "USB1") (pin "A11") (pinfunction "RX2+_A11") (pintype "passive"))
    )
    (net (code "98") (name "unconnected-(USB1-RX2--PadA10)") (class "Default")
      (node (ref "USB1") (pin "A10") (pinfunction "RX2-_A10") (pintype "passive"))
    )
    (net (code "99") (name "unconnected-(USB1-SBU1-PadA8)") (class "Default")
      (node (ref "USB1") (pin "A8") (pinfunction "SBU1_A8") (pintype "passive"))
    )
    (net (code "100") (name "unconnected-(USB1-SBU2-PadB8)") (class "Default")
      (node (ref "USB1") (pin "B8") (pinfunction "SBU2_B8") (pintype "passive"))
    )
    (net (code "101") (name "unconnected-(USB1-TX1+-PadA2)") (class "Default")
      (node (ref "USB1") (pin "A2") (pinfunction "TX1+_A2") (pintype "passive"))
    )
    (net (code "102") (name "unconnected-(USB1-TX1--PadA3)") (class "Default")
      (node (ref "USB1") (pin "A3") (pinfunction "TX1-_A3") (pintype "passive"))
    )
    (net (code "103") (name "unconnected-(USB1-TX2+-PadB2)") (class "Default")
      (node (ref "USB1") (pin "B2") (pinfunction "TX2+_B2") (pintype "passive"))
    )
    (net (code "104") (name "unconnected-(USB1-TX2--PadB3)") (class "Default")
      (node (ref "USB1") (pin "B3") (pinfunction "TX2-_B3") (pintype "passive"))
    )
  )
)
